# LVDS_IFC_MCX.net
KiCad netlist of a schematic drawn in Altium Designer
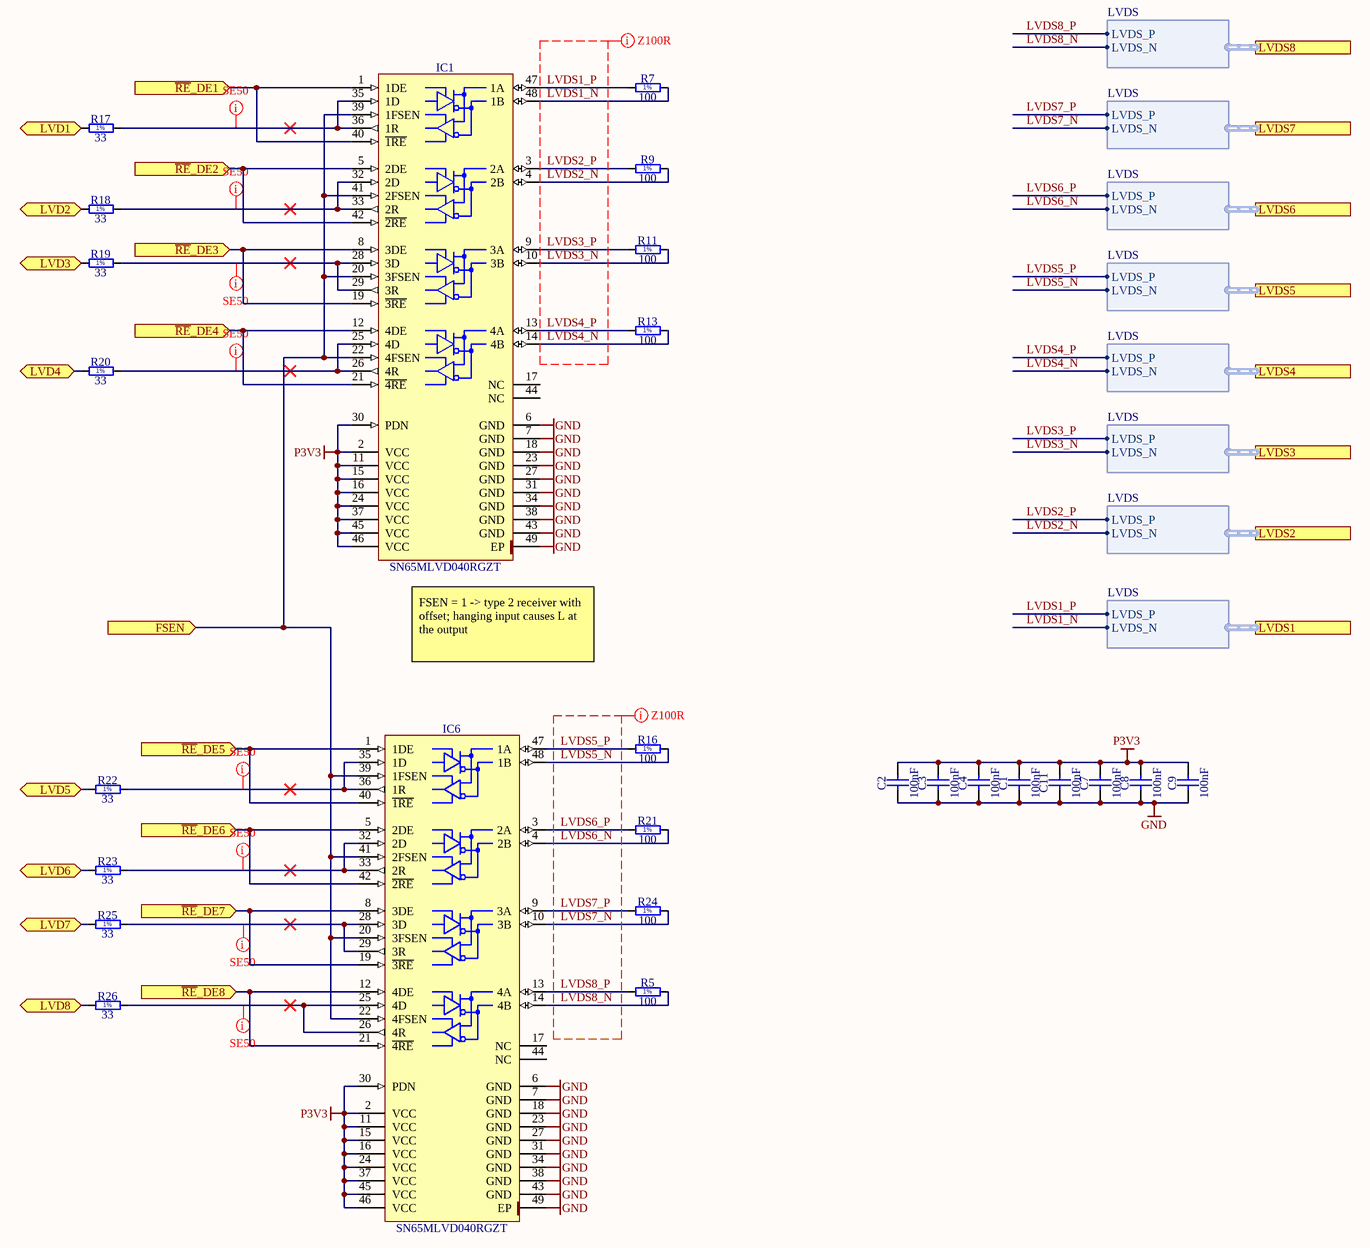
[diagram p0: LVDS_IFC_MCX.SchDoc]

(export (version "E")
  (design (tool "Eeschema 10.0.6"))
  (components
    (comp (ref "C1")
      (value "100nF")
      (footprint "CAPC1005X55N")
      (description "Non-polarised capacitor")
      (fields
        (field (name "PART NUMBER") "CC0402_100NF_16V_10%_X5R")
        (field (name "VOLTAGE") "16V")
        (field (name "AUTHOR") "CERN DEM JLC")
      )
      (libsource (lib "Capacitors") (part "Capacitor - non polarized"))
    )
    (comp (ref "C2")
      (value "100nF")
      (footprint "CAPC1005X55N")
      (description "Non-polarised capacitor")
      (fields
        (field (name "PART NUMBER") "CC0402_100NF_16V_10%_X5R")
        (field (name "VOLTAGE") "16V")
        (field (name "AUTHOR") "CERN DEM JLC")
      )
      (libsource (lib "Capacitors") (part "Capacitor - non polarized"))
    )
    (comp (ref "C3")
      (value "100nF")
      (footprint "CAPC1005X55N")
      (description "Non-polarised capacitor")
      (fields
        (field (name "PART NUMBER") "CC0402_100NF_16V_10%_X5R")
        (field (name "VOLTAGE") "16V")
        (field (name "AUTHOR") "CERN DEM JLC")
      )
      (libsource (lib "Capacitors") (part "Capacitor - non polarized"))
    )
    (comp (ref "C4")
      (value "100nF")
      (footprint "CAPC1005X55N")
      (description "Non-polarised capacitor")
      (fields
        (field (name "PART NUMBER") "CC0402_100NF_16V_10%_X5R")
        (field (name "VOLTAGE") "16V")
        (field (name "AUTHOR") "CERN DEM JLC")
      )
      (libsource (lib "Capacitors") (part "Capacitor - non polarized"))
    )
    (comp (ref "C7")
      (value "100nF")
      (footprint "CAPC1005X55N")
      (description "Non-polarised capacitor")
      (fields
        (field (name "PART NUMBER") "CC0402_100NF_16V_10%_X5R")
        (field (name "VOLTAGE") "16V")
        (field (name "AUTHOR") "CERN DEM JLC")
      )
      (libsource (lib "Capacitors") (part "Capacitor - non polarized"))
    )
    (comp (ref "C8")
      (value "100nF")
      (footprint "CAPC1005X55N")
      (description "Non-polarised capacitor")
      (fields
        (field (name "PART NUMBER") "CC0402_100NF_16V_10%_X5R")
        (field (name "VOLTAGE") "16V")
        (field (name "AUTHOR") "CERN DEM JLC")
      )
      (libsource (lib "Capacitors") (part "Capacitor - non polarized"))
    )
    (comp (ref "C9")
      (value "100nF")
      (footprint "CAPC1005X55N")
      (description "Non-polarised capacitor")
      (fields
        (field (name "PART NUMBER") "CC0402_100NF_16V_10%_X5R")
        (field (name "VOLTAGE") "16V")
        (field (name "AUTHOR") "CERN DEM JLC")
      )
      (libsource (lib "Capacitors") (part "Capacitor - non polarized"))
    )
    (comp (ref "C11")
      (value "100nF")
      (footprint "CAPC1005X55N")
      (description "Non-polarised capacitor")
      (fields
        (field (name "PART NUMBER") "CC0402_100NF_16V_10%_X5R")
        (field (name "VOLTAGE") "16V")
        (field (name "AUTHOR") "CERN DEM JLC")
      )
      (libsource (lib "Capacitors") (part "Capacitor - non polarized"))
    )
    (comp (ref "IC1")
      (value "SN65MLVD040RGZT")
      (footprint "QFN50P700X700X100-49N-S420")
      (description "4-Channel Half-Duplex M-LVDS Line Transceiver")
      (fields (field (name "MANUFACTURER") "TEXAS INSTRUMENTS") (field (name "AUTHOR") "CERN DEM JLC"))
      (libsource (lib "ICs And Semiconductors") (part "SN65MLVD040"))
    )
    (comp (ref "IC6")
      (value "SN65MLVD040RGZT")
      (footprint "QFN50P700X700X100-49N-S420")
      (description "4-Channel Half-Duplex M-LVDS Line Transceiver")
      (fields (field (name "MANUFACTURER") "TEXAS INSTRUMENTS") (field (name "AUTHOR") "CERN DEM JLC"))
      (libsource (lib "ICs And Semiconductors") (part "SN65MLVD040"))
    )
    (comp (ref "R5")
      (value "100")
      (footprint "RESC1005X40N")
      (description "Resistor - 1%")
      (fields
        (field (name "PART NUMBER") "R0402_100R_1%_0.1W_100PPM")
        (field (name "POWER") "0.1W")
        (field (name "AUTHOR") "CERN DEM JLC")
      )
      (libsource (lib "Resistors") (part "Resistor - 1%"))
    )
    (comp (ref "R7")
      (value "100")
      (footprint "RESC1005X40N")
      (description "Resistor - 1%")
      (fields
        (field (name "PART NUMBER") "R0402_100R_1%_0.1W_100PPM")
        (field (name "POWER") "0.1W")
        (field (name "AUTHOR") "CERN DEM JLC")
      )
      (libsource (lib "Resistors") (part "Resistor - 1%"))
    )
    (comp (ref "R9")
      (value "100")
      (footprint "RESC1005X40N")
      (description "Resistor - 1%")
      (fields
        (field (name "PART NUMBER") "R0402_100R_1%_0.1W_100PPM")
        (field (name "POWER") "0.1W")
        (field (name "AUTHOR") "CERN DEM JLC")
      )
      (libsource (lib "Resistors") (part "Resistor - 1%"))
    )
    (comp (ref "R11")
      (value "100")
      (footprint "RESC1005X40N")
      (description "Resistor - 1%")
      (fields
        (field (name "PART NUMBER") "R0402_100R_1%_0.1W_100PPM")
        (field (name "POWER") "0.1W")
        (field (name "AUTHOR") "CERN DEM JLC")
      )
      (libsource (lib "Resistors") (part "Resistor - 1%"))
    )
    (comp (ref "R13")
      (value "100")
      (footprint "RESC1005X40N")
      (description "Resistor - 1%")
      (fields
        (field (name "PART NUMBER") "R0402_100R_1%_0.1W_100PPM")
        (field (name "POWER") "0.1W")
        (field (name "AUTHOR") "CERN DEM JLC")
      )
      (libsource (lib "Resistors") (part "Resistor - 1%"))
    )
    (comp (ref "R16")
      (value "100")
      (footprint "RESC1005X40N")
      (description "Resistor - 1%")
      (fields
        (field (name "PART NUMBER") "R0402_100R_1%_0.1W_100PPM")
        (field (name "POWER") "0.1W")
        (field (name "AUTHOR") "CERN DEM JLC")
      )
      (libsource (lib "Resistors") (part "Resistor - 1%"))
    )
    (comp (ref "R17")
      (value "33")
      (footprint "RESC1005X40N")
      (description "Resistor - 1%")
      (fields
        (field (name "PART NUMBER") "R0402_33R_1%_0.0625W_100PPM")
        (field (name "POWER") "0.0625W")
        (field (name "AUTHOR") "CERN DEM JLC")
      )
      (libsource (lib "Resistors") (part "Resistor - 1%"))
    )
    (comp (ref "R18")
      (value "33")
      (footprint "RESC1005X40N")
      (description "Resistor - 1%")
      (fields
        (field (name "PART NUMBER") "R0402_33R_1%_0.0625W_100PPM")
        (field (name "POWER") "0.0625W")
        (field (name "AUTHOR") "CERN DEM JLC")
      )
      (libsource (lib "Resistors") (part "Resistor - 1%"))
    )
    (comp (ref "R19")
      (value "33")
      (footprint "RESC1005X40N")
      (description "Resistor - 1%")
      (fields
        (field (name "PART NUMBER") "R0402_33R_1%_0.0625W_100PPM")
        (field (name "POWER") "0.0625W")
        (field (name "AUTHOR") "CERN DEM JLC")
      )
      (libsource (lib "Resistors") (part "Resistor - 1%"))
    )
    (comp (ref "R20")
      (value "33")
      (footprint "RESC1005X40N")
      (description "Resistor - 1%")
      (fields
        (field (name "PART NUMBER") "R0402_33R_1%_0.0625W_100PPM")
        (field (name "POWER") "0.0625W")
        (field (name "AUTHOR") "CERN DEM JLC")
      )
      (libsource (lib "Resistors") (part "Resistor - 1%"))
    )
    (comp (ref "R21")
      (value "100")
      (footprint "RESC1005X40N")
      (description "Resistor - 1%")
      (fields
        (field (name "PART NUMBER") "R0402_100R_1%_0.1W_100PPM")
        (field (name "POWER") "0.1W")
        (field (name "AUTHOR") "CERN DEM JLC")
      )
      (libsource (lib "Resistors") (part "Resistor - 1%"))
    )
    (comp (ref "R22")
      (value "33")
      (footprint "RESC1005X40N")
      (description "Resistor - 1%")
      (fields
        (field (name "PART NUMBER") "R0402_33R_1%_0.0625W_100PPM")
        (field (name "POWER") "0.0625W")
        (field (name "AUTHOR") "CERN DEM JLC")
      )
      (libsource (lib "Resistors") (part "Resistor - 1%"))
    )
    (comp (ref "R23")
      (value "33")
      (footprint "RESC1005X40N")
      (description "Resistor - 1%")
      (fields
        (field (name "PART NUMBER") "R0402_33R_1%_0.0625W_100PPM")
        (field (name "POWER") "0.0625W")
        (field (name "AUTHOR") "CERN DEM JLC")
      )
      (libsource (lib "Resistors") (part "Resistor - 1%"))
    )
    (comp (ref "R24")
      (value "100")
      (footprint "RESC1005X40N")
      (description "Resistor - 1%")
      (fields
        (field (name "PART NUMBER") "R0402_100R_1%_0.1W_100PPM")
        (field (name "POWER") "0.1W")
        (field (name "AUTHOR") "CERN DEM JLC")
      )
      (libsource (lib "Resistors") (part "Resistor - 1%"))
    )
    (comp (ref "R25")
      (value "33")
      (footprint "RESC1005X40N")
      (description "Resistor - 1%")
      (fields
        (field (name "PART NUMBER") "R0402_33R_1%_0.0625W_100PPM")
        (field (name "POWER") "0.0625W")
        (field (name "AUTHOR") "CERN DEM JLC")
      )
      (libsource (lib "Resistors") (part "Resistor - 1%"))
    )
    (comp (ref "R26")
      (value "33")
      (footprint "RESC1005X40N")
      (description "Resistor - 1%")
      (fields
        (field (name "PART NUMBER") "R0402_33R_1%_0.0625W_100PPM")
        (field (name "POWER") "0.0625W")
        (field (name "AUTHOR") "CERN DEM JLC")
      )
      (libsource (lib "Resistors") (part "Resistor - 1%"))
    )
  )
  (nets
    (net (code "2") (name "/FSEN") (class "Default")
      (node (ref "IC1") (pin "20") (pinfunction "3FSEN_20") (pintype "input"))
      (node (ref "IC1") (pin "22") (pinfunction "4FSEN_22") (pintype "input"))
      (node (ref "IC1") (pin "39") (pinfunction "1FSEN_39") (pintype "input"))
      (node (ref "IC1") (pin "41") (pinfunction "2FSEN_41") (pintype "input"))
      (node (ref "IC6") (pin "20") (pinfunction "3FSEN_20") (pintype "input"))
      (node (ref "IC6") (pin "22") (pinfunction "4FSEN_22") (pintype "input"))
      (node (ref "IC6") (pin "39") (pinfunction "1FSEN_39") (pintype "input"))
      (node (ref "IC6") (pin "41") (pinfunction "2FSEN_41") (pintype "input"))
    )
    (net (code "3") (name "/LVD1") (class "Default")
      (node (ref "R17") (pin "1") (pinfunction "1_1") (pintype "passive"))
    )
    (net (code "4") (name "/LVD2") (class "Default")
      (node (ref "R18") (pin "1") (pinfunction "1_1") (pintype "passive"))
    )
    (net (code "5") (name "/LVD3") (class "Default")
      (node (ref "R19") (pin "1") (pinfunction "1_1") (pintype "passive"))
    )
    (net (code "6") (name "/LVD4") (class "Default")
      (node (ref "R20") (pin "1") (pinfunction "1_1") (pintype "passive"))
    )
    (net (code "7") (name "/LVD5") (class "Default")
      (node (ref "R22") (pin "1") (pinfunction "1_1") (pintype "passive"))
    )
    (net (code "8") (name "/LVD6") (class "Default")
      (node (ref "R23") (pin "1") (pinfunction "1_1") (pintype "passive"))
    )
    (net (code "9") (name "/LVD7") (class "Default")
      (node (ref "R25") (pin "1") (pinfunction "1_1") (pintype "passive"))
    )
    (net (code "10") (name "/LVD8") (class "Default")
      (node (ref "R26") (pin "1") (pinfunction "1_1") (pintype "passive"))
    )
    (net (code "11") (name "/LVDS1_N") (class "Default")
      (node (ref "IC1") (pin "48") (pinfunction "1B_48") (pintype "bidirectional"))
      (node (ref "R7") (pin "2") (pinfunction "2_2") (pintype "passive"))
    )
    (net (code "12") (name "/LVDS1_P") (class "Default")
      (node (ref "IC1") (pin "47") (pinfunction "1A_47") (pintype "bidirectional"))
      (node (ref "R7") (pin "1") (pinfunction "1_1") (pintype "passive"))
    )
    (net (code "13") (name "/LVDS2_N") (class "Default")
      (node (ref "IC1") (pin "4") (pinfunction "2B_4") (pintype "bidirectional"))
      (node (ref "R9") (pin "2") (pinfunction "2_2") (pintype "passive"))
    )
    (net (code "14") (name "/LVDS2_P") (class "Default")
      (node (ref "IC1") (pin "3") (pinfunction "2A_3") (pintype "bidirectional"))
      (node (ref "R9") (pin "1") (pinfunction "1_1") (pintype "passive"))
    )
    (net (code "15") (name "/LVDS3_N") (class "Default")
      (node (ref "IC1") (pin "10") (pinfunction "3B_10") (pintype "bidirectional"))
      (node (ref "R11") (pin "2") (pinfunction "2_2") (pintype "passive"))
    )
    (net (code "16") (name "/LVDS3_P") (class "Default")
      (node (ref "IC1") (pin "9") (pinfunction "3A_9") (pintype "bidirectional"))
      (node (ref "R11") (pin "1") (pinfunction "1_1") (pintype "passive"))
    )
    (net (code "17") (name "/LVDS4_N") (class "Default")
      (node (ref "IC1") (pin "14") (pinfunction "4B_14") (pintype "bidirectional"))
      (node (ref "R13") (pin "2") (pinfunction "2_2") (pintype "passive"))
    )
    (net (code "18") (name "/LVDS4_P") (class "Default")
      (node (ref "IC1") (pin "13") (pinfunction "4A_13") (pintype "bidirectional"))
      (node (ref "R13") (pin "1") (pinfunction "1_1") (pintype "passive"))
    )
    (net (code "19") (name "/LVDS5_N") (class "Default")
      (node (ref "IC6") (pin "48") (pinfunction "1B_48") (pintype "bidirectional"))
      (node (ref "R16") (pin "2") (pinfunction "2_2") (pintype "passive"))
    )
    (net (code "20") (name "/LVDS5_P") (class "Default")
      (node (ref "IC6") (pin "47") (pinfunction "1A_47") (pintype "bidirectional"))
      (node (ref "R16") (pin "1") (pinfunction "1_1") (pintype "passive"))
    )
    (net (code "21") (name "/LVDS6_N") (class "Default")
      (node (ref "IC6") (pin "4") (pinfunction "2B_4") (pintype "bidirectional"))
      (node (ref "R21") (pin "2") (pinfunction "2_2") (pintype "passive"))
    )
    (net (code "22") (name "/LVDS6_P") (class "Default")
      (node (ref "IC6") (pin "3") (pinfunction "2A_3") (pintype "bidirectional"))
      (node (ref "R21") (pin "1") (pinfunction "1_1") (pintype "passive"))
    )
    (net (code "23") (name "/LVDS7_N") (class "Default")
      (node (ref "IC6") (pin "10") (pinfunction "3B_10") (pintype "bidirectional"))
      (node (ref "R24") (pin "2") (pinfunction "2_2") (pintype "passive"))
    )
    (net (code "24") (name "/LVDS7_P") (class "Default")
      (node (ref "IC6") (pin "9") (pinfunction "3A_9") (pintype "bidirectional"))
      (node (ref "R24") (pin "1") (pinfunction "1_1") (pintype "passive"))
    )
    (net (code "25") (name "/LVDS8_N") (class "Default")
      (node (ref "IC6") (pin "14") (pinfunction "4B_14") (pintype "bidirectional"))
      (node (ref "R5") (pin "2") (pinfunction "2_2") (pintype "passive"))
    )
    (net (code "26") (name "/LVDS8_P") (class "Default")
      (node (ref "IC6") (pin "13") (pinfunction "4A_13") (pintype "bidirectional"))
      (node (ref "R5") (pin "1") (pinfunction "1_1") (pintype "passive"))
    )
    (net (code "28") (name "/~{RE}_DE1") (class "Default")
      (node (ref "IC1") (pin "1") (pinfunction "1DE_1") (pintype "input"))
      (node (ref "IC1") (pin "40") (pinfunction "~{1RE}_40") (pintype "input"))
    )
    (net (code "29") (name "/~{RE}_DE2") (class "Default")
      (node (ref "IC1") (pin "42") (pinfunction "~{2RE}_42") (pintype "input"))
      (node (ref "IC1") (pin "5") (pinfunction "2DE_5") (pintype "input"))
    )
    (net (code "30") (name "/~{RE}_DE3") (class "Default")
      (node (ref "IC1") (pin "19") (pinfunction "~{3RE}_19") (pintype "input"))
      (node (ref "IC1") (pin "8") (pinfunction "3DE_8") (pintype "input"))
    )
    (net (code "31") (name "/~{RE}_DE4") (class "Default")
      (node (ref "IC1") (pin "12") (pinfunction "4DE_12") (pintype "input"))
      (node (ref "IC1") (pin "21") (pinfunction "~{4RE}_21") (pintype "input"))
    )
    (net (code "32") (name "/~{RE}_DE5") (class "Default")
      (node (ref "IC6") (pin "1") (pinfunction "1DE_1") (pintype "input"))
      (node (ref "IC6") (pin "40") (pinfunction "~{1RE}_40") (pintype "input"))
    )
    (net (code "33") (name "/~{RE}_DE6") (class "Default")
      (node (ref "IC6") (pin "42") (pinfunction "~{2RE}_42") (pintype "input"))
      (node (ref "IC6") (pin "5") (pinfunction "2DE_5") (pintype "input"))
    )
    (net (code "34") (name "/~{RE}_DE7") (class "Default")
      (node (ref "IC6") (pin "19") (pinfunction "~{3RE}_19") (pintype "input"))
      (node (ref "IC6") (pin "8") (pinfunction "3DE_8") (pintype "input"))
    )
    (net (code "35") (name "/~{RE}_DE8") (class "Default")
      (node (ref "IC6") (pin "12") (pinfunction "4DE_12") (pintype "input"))
      (node (ref "IC6") (pin "21") (pinfunction "~{4RE}_21") (pintype "input"))
    )
    (net (code "36") (name "GND") (class "Default")
      (node (ref "C1") (pin "1") (pinfunction "1_1") (pintype "passive"))
      (node (ref "C11") (pin "1") (pinfunction "1_1") (pintype "passive"))
      (node (ref "C2") (pin "1") (pinfunction "1_1") (pintype "passive"))
      (node (ref "C3") (pin "1") (pinfunction "1_1") (pintype "passive"))
      (node (ref "C4") (pin "1") (pinfunction "1_1") (pintype "passive"))
      (node (ref "C7") (pin "1") (pinfunction "1_1") (pintype "passive"))
      (node (ref "C8") (pin "1") (pinfunction "1_1") (pintype "passive"))
      (node (ref "C9") (pin "1") (pinfunction "1_1") (pintype "passive"))
      (node (ref "IC1") (pin "18") (pinfunction "GND_18") (pintype "power_in"))
      (node (ref "IC1") (pin "23") (pinfunction "GND_23") (pintype "power_in"))
      (node (ref "IC1") (pin "27") (pinfunction "GND_27") (pintype "power_in"))
      (node (ref "IC1") (pin "31") (pinfunction "GND_31") (pintype "power_in"))
      (node (ref "IC1") (pin "34") (pinfunction "GND_34") (pintype "power_in"))
      (node (ref "IC1") (pin "38") (pinfunction "GND_38") (pintype "power_in"))
      (node (ref "IC1") (pin "43") (pinfunction "GND_43") (pintype "power_in"))
      (node (ref "IC1") (pin "49") (pinfunction "EP_49") (pintype "power_in"))
      (node (ref "IC1") (pin "6") (pinfunction "GND_6") (pintype "power_in"))
      (node (ref "IC1") (pin "7") (pinfunction "GND_7") (pintype "power_in"))
      (node (ref "IC6") (pin "18") (pinfunction "GND_18") (pintype "power_in"))
      (node (ref "IC6") (pin "23") (pinfunction "GND_23") (pintype "power_in"))
      (node (ref "IC6") (pin "27") (pinfunction "GND_27") (pintype "power_in"))
      (node (ref "IC6") (pin "31") (pinfunction "GND_31") (pintype "power_in"))
      (node (ref "IC6") (pin "34") (pinfunction "GND_34") (pintype "power_in"))
      (node (ref "IC6") (pin "38") (pinfunction "GND_38") (pintype "power_in"))
      (node (ref "IC6") (pin "43") (pinfunction "GND_43") (pintype "power_in"))
      (node (ref "IC6") (pin "49") (pinfunction "EP_49") (pintype "power_in"))
      (node (ref "IC6") (pin "6") (pinfunction "GND_6") (pintype "power_in"))
      (node (ref "IC6") (pin "7") (pinfunction "GND_7") (pintype "power_in"))
    )
    (net (code "37") (name "Net-(IC1-1D)") (class "Default")
      (node (ref "IC1") (pin "35") (pinfunction "1D_35") (pintype "input"))
      (node (ref "IC1") (pin "36") (pinfunction "1R_36") (pintype "output"))
      (node (ref "R17") (pin "2") (pinfunction "2_2") (pintype "passive"))
    )
    (net (code "38") (name "Net-(IC1-2D)") (class "Default")
      (node (ref "IC1") (pin "32") (pinfunction "2D_32") (pintype "input"))
      (node (ref "IC1") (pin "33") (pinfunction "2R_33") (pintype "output"))
      (node (ref "R18") (pin "2") (pinfunction "2_2") (pintype "passive"))
    )
    (net (code "39") (name "Net-(IC1-3D)") (class "Default")
      (node (ref "IC1") (pin "28") (pinfunction "3D_28") (pintype "input"))
      (node (ref "IC1") (pin "29") (pinfunction "3R_29") (pintype "output"))
      (node (ref "R19") (pin "2") (pinfunction "2_2") (pintype "passive"))
    )
    (net (code "40") (name "Net-(IC1-4D)") (class "Default")
      (node (ref "IC1") (pin "25") (pinfunction "4D_25") (pintype "input"))
      (node (ref "IC1") (pin "26") (pinfunction "4R_26") (pintype "output"))
      (node (ref "R20") (pin "2") (pinfunction "2_2") (pintype "passive"))
    )
    (net (code "41") (name "Net-(IC6-1D)") (class "Default")
      (node (ref "IC6") (pin "35") (pinfunction "1D_35") (pintype "input"))
      (node (ref "IC6") (pin "36") (pinfunction "1R_36") (pintype "output"))
      (node (ref "R22") (pin "2") (pinfunction "2_2") (pintype "passive"))
    )
    (net (code "42") (name "Net-(IC6-2D)") (class "Default")
      (node (ref "IC6") (pin "32") (pinfunction "2D_32") (pintype "input"))
      (node (ref "IC6") (pin "33") (pinfunction "2R_33") (pintype "output"))
      (node (ref "R23") (pin "2") (pinfunction "2_2") (pintype "passive"))
    )
    (net (code "43") (name "Net-(IC6-3D)") (class "Default")
      (node (ref "IC6") (pin "28") (pinfunction "3D_28") (pintype "input"))
      (node (ref "IC6") (pin "29") (pinfunction "3R_29") (pintype "output"))
      (node (ref "R25") (pin "2") (pinfunction "2_2") (pintype "passive"))
    )
    (net (code "44") (name "Net-(IC6-4D)") (class "Default")
      (node (ref "IC6") (pin "25") (pinfunction "4D_25") (pintype "input"))
      (node (ref "IC6") (pin "26") (pinfunction "4R_26") (pintype "output"))
      (node (ref "R26") (pin "2") (pinfunction "2_2") (pintype "passive"))
    )
    (net (code "45") (name "P3V3") (class "Default")
      (node (ref "C1") (pin "2") (pinfunction "2_2") (pintype "passive"))
      (node (ref "C11") (pin "2") (pinfunction "2_2") (pintype "passive"))
      (node (ref "C2") (pin "2") (pinfunction "2_2") (pintype "passive"))
      (node (ref "C3") (pin "2") (pinfunction "2_2") (pintype "passive"))
      (node (ref "C4") (pin "2") (pinfunction "2_2") (pintype "passive"))
      (node (ref "C7") (pin "2") (pinfunction "2_2") (pintype "passive"))
      (node (ref "C8") (pin "2") (pinfunction "2_2") (pintype "passive"))
      (node (ref "C9") (pin "2") (pinfunction "2_2") (pintype "passive"))
      (node (ref "IC1") (pin "11") (pinfunction "VCC_11") (pintype "power_in"))
      (node (ref "IC1") (pin "15") (pinfunction "VCC_15") (pintype "power_in"))
      (node (ref "IC1") (pin "16") (pinfunction "VCC_16") (pintype "power_in"))
      (node (ref "IC1") (pin "2") (pinfunction "VCC_2") (pintype "power_in"))
      (node (ref "IC1") (pin "24") (pinfunction "VCC_24") (pintype "power_in"))
      (node (ref "IC1") (pin "30") (pinfunction "PDN_30") (pintype "input"))
      (node (ref "IC1") (pin "37") (pinfunction "VCC_37") (pintype "power_in"))
      (node (ref "IC1") (pin "45") (pinfunction "VCC_45") (pintype "power_in"))
      (node (ref "IC1") (pin "46") (pinfunction "VCC_46") (pintype "power_in"))
      (node (ref "IC6") (pin "11") (pinfunction "VCC_11") (pintype "power_in"))
      (node (ref "IC6") (pin "15") (pinfunction "VCC_15") (pintype "power_in"))
      (node (ref "IC6") (pin "16") (pinfunction "VCC_16") (pintype "power_in"))
      (node (ref "IC6") (pin "2") (pinfunction "VCC_2") (pintype "power_in"))
      (node (ref "IC6") (pin "24") (pinfunction "VCC_24") (pintype "power_in"))
      (node (ref "IC6") (pin "30") (pinfunction "PDN_30") (pintype "input"))
      (node (ref "IC6") (pin "37") (pinfunction "VCC_37") (pintype "power_in"))
      (node (ref "IC6") (pin "45") (pinfunction "VCC_45") (pintype "power_in"))
      (node (ref "IC6") (pin "46") (pinfunction "VCC_46") (pintype "power_in"))
    )
    (net (code "46") (name "unconnected-(IC1-NC-Pad17)") (class "Default")
      (node (ref "IC1") (pin "17") (pinfunction "NC_17") (pintype "passive"))
    )
    (net (code "47") (name "unconnected-(IC1-NC-Pad44)") (class "Default")
      (node (ref "IC1") (pin "44") (pinfunction "NC_44") (pintype "passive"))
    )
    (net (code "48") (name "unconnected-(IC6-NC-Pad17)") (class "Default")
      (node (ref "IC6") (pin "17") (pinfunction "NC_17") (pintype "passive"))
    )
    (net (code "49") (name "unconnected-(IC6-NC-Pad44)") (class "Default")
      (node (ref "IC6") (pin "44") (pinfunction "NC_44") (pintype "passive"))
    )
  )
)
